# FLASH.net
KiCad netlist of a schematic drawn in Altium Designer
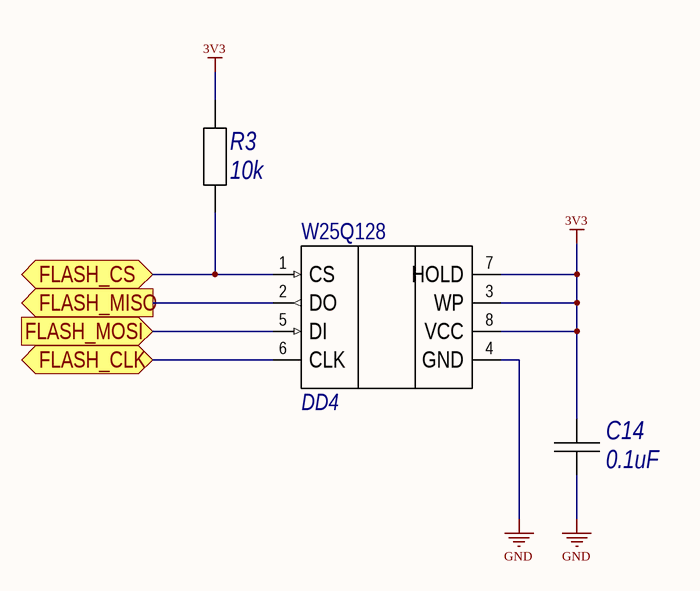
[diagram p0: FLASH.SchDoc]

(export (version "E")
  (design (tool "Eeschema 10.0.6"))
  (components
    (comp (ref "C14")
      (value "0.1uF")
      (footprint "C0805C")
      (fields (field (name "PUBLISHER") "Andrew Danich"))
      (libsource (lib "PA_control_board") (part "CAP_0805"))
    )
    (comp (ref "DD4")
      (value "W25Q128")
      (footprint "SOIC8 (SO-8)")
      (libsource (lib "PA_control_board") (part "W25Q128"))
    )
    (comp (ref "R3")
      (value "10k")
      (footprint "C0805R")
      (fields (field (name "PUBLISHER") "Andrew Danich"))
      (libsource (lib "PA_control_board") (part "RES_0805"))
    )
  )
  (nets
    (net (code "1") (name "/FLASH_CLK") (class "Default")
      (node (ref "DD4") (pin "6") (pinfunction "CLK_6") (pintype "passive"))
    )
    (net (code "2") (name "/FLASH_CS") (class "Default")
      (node (ref "DD4") (pin "1") (pinfunction "CS_1") (pintype "input"))
      (node (ref "R3") (pin "1") (pinfunction "1_1") (pintype "passive"))
    )
    (net (code "3") (name "/FLASH_MISO") (class "Default")
      (node (ref "DD4") (pin "2") (pinfunction "DO_2") (pintype "output"))
    )
    (net (code "4") (name "/FLASH_MOSI") (class "Default")
      (node (ref "DD4") (pin "5") (pinfunction "DI_5") (pintype "input"))
    )
    (net (code "5") (name "3V3") (class "Default")
      (node (ref "C14") (pin "2") (pinfunction "2_2") (pintype "passive"))
      (node (ref "DD4") (pin "3") (pinfunction "WP_3") (pintype "passive"))
      (node (ref "DD4") (pin "7") (pinfunction "HOLD_7") (pintype "passive"))
      (node (ref "DD4") (pin "8") (pinfunction "VCC_8") (pintype "power_in"))
      (node (ref "R3") (pin "2") (pinfunction "2_2") (pintype "passive"))
    )
    (net (code "6") (name "GND") (class "Default")
      (node (ref "C14") (pin "1") (pinfunction "1_1") (pintype "passive"))
      (node (ref "DD4") (pin "4") (pinfunction "GND_4") (pintype "passive"))
    )
  )
)
